# BrakePlaus2019.net
KiCad netlist of a schematic drawn in Altium Designer
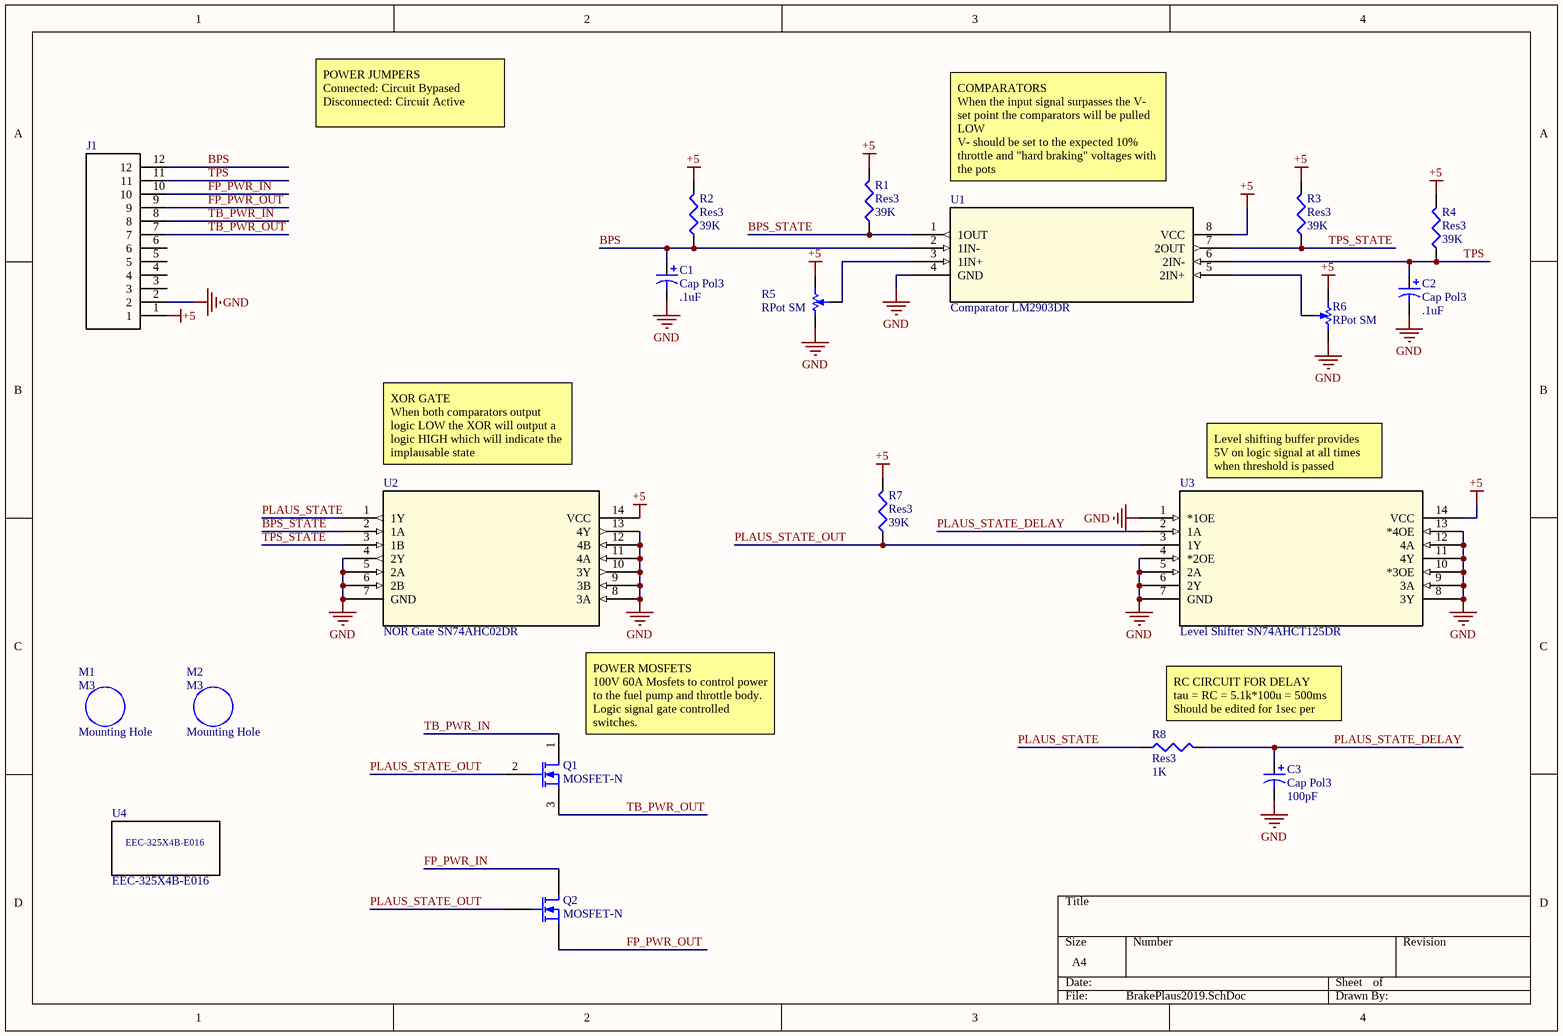
[diagram p0: BrakePlaus2019.SchDoc]

(export (version "E")
  (design (tool "Eeschema 10.0.6"))
  (components
    (comp (ref "C1")
      (value "Cap Pol3")
      (footprint "C0805")
      (description "Polarized Capacitor (Surface Mount)")
      (fields (field (name "ALTIUM_VALUE") ".1uF") (field (name "PUBLISHER") "Altium Limited"))
      (libsource (lib "Miscellaneous Devices") (part "Cap Pol3"))
    )
    (comp (ref "C2")
      (value "Cap Pol3")
      (footprint "C0805")
      (description "Polarized Capacitor (Surface Mount)")
      (fields (field (name "ALTIUM_VALUE") ".1uF") (field (name "PUBLISHER") "Altium Limited"))
      (libsource (lib "Miscellaneous Devices") (part "Cap Pol3"))
    )
    (comp (ref "C3")
      (value "Cap Pol3")
      (footprint "C0805")
      (description "Polarized Capacitor (Surface Mount)")
      (fields (field (name "ALTIUM_VALUE") "100pF") (field (name "PUBLISHER") "Altium Limited"))
      (libsource (lib "Miscellaneous Devices") (part "Cap Pol3"))
    )
    (comp (ref "J1")
      (value "DTM13-12PA-R008")
      (footprint "*TE_DTM13-12PA-R008")
      (description "DTM Series, 4.19mm Pitch 12 Way 2 Row Right Angle PCB Header, Solder Termination")
      (fields (field (name "MF") "TE Connectivity") (field (name "DIGI-KEY_PART_NUMBER") "1734-1130-ND"))
      (libsource (lib "DTM13-12PA-R008") (part "DTM13-12PA-R008"))
    )
    (comp (ref "M1")
      (value "Mounting Hole")
      (footprint "M3 Mounting Hole")
      (libsource (lib "BrakePlaus2019") (part "M3 Mounting Hole"))
    )
    (comp (ref "M2")
      (value "Mounting Hole")
      (footprint "M3 Mounting Hole")
      (libsource (lib "BrakePlaus2019") (part "M3 Mounting Hole"))
    )
    (comp (ref "Q1")
      (value "MOSFET-N")
      (footprint "DPAK")
      (description "N-Channel MOSFET")
      (fields (field (name "PUBLISHER") "Altium Limited"))
      (libsource (lib "Miscellaneous Devices") (part "MOSFET-N"))
    )
    (comp (ref "Q2")
      (value "MOSFET-N")
      (footprint "DPAK")
      (description "N-Channel MOSFET")
      (fields (field (name "PUBLISHER") "Altium Limited"))
      (libsource (lib "") (part "MOSFET-N_1"))
    )
    (comp (ref "R1")
      (value "Res3")
      (footprint "J1-0603")
      (description "Resistor")
      (fields (field (name "ALTIUM_VALUE") "39K") (field (name "PUBLISHER") "Altium Limited"))
      (libsource (lib "Miscellaneous Devices") (part "Res3"))
    )
    (comp (ref "R2")
      (value "Res3")
      (footprint "J1-0603")
      (description "Resistor")
      (fields (field (name "ALTIUM_VALUE") "39K") (field (name "PUBLISHER") "Altium Limited"))
      (libsource (lib "Miscellaneous Devices") (part "Res3"))
    )
    (comp (ref "R3")
      (value "Res3")
      (footprint "J1-0603")
      (description "Resistor")
      (fields (field (name "ALTIUM_VALUE") "39K") (field (name "PUBLISHER") "Altium Limited"))
      (libsource (lib "Miscellaneous Devices") (part "Res3"))
    )
    (comp (ref "R4")
      (value "Res3")
      (footprint "J1-0603")
      (description "Resistor")
      (fields (field (name "ALTIUM_VALUE") "39K") (field (name "PUBLISHER") "Altium Limited"))
      (libsource (lib "Miscellaneous Devices") (part "Res3"))
    )
    (comp (ref "R5")
      (value "RPot SM")
      (footprint "POT4MM-2")
      (description "Square Trimming Potentiometer")
      (fields (field (name "PUBLISHER") "Altium Limited"))
      (libsource (lib "Miscellaneous Devices") (part "RPot SM"))
    )
    (comp (ref "R6")
      (value "RPot SM")
      (footprint "POT4MM-2")
      (description "Square Trimming Potentiometer")
      (fields (field (name "PUBLISHER") "Altium Limited"))
      (libsource (lib "Miscellaneous Devices") (part "RPot SM"))
    )
    (comp (ref "R7")
      (value "Res3")
      (footprint "J1-0603")
      (description "Resistor")
      (fields (field (name "ALTIUM_VALUE") "39K") (field (name "PUBLISHER") "Altium Limited"))
      (libsource (lib "Miscellaneous Devices") (part "Res3"))
    )
    (comp (ref "R8")
      (value "Res3")
      (footprint "J1-0603")
      (description "Resistor")
      (fields (field (name "ALTIUM_VALUE") "1K") (field (name "PUBLISHER") "Altium Limited"))
      (libsource (lib "Miscellaneous Devices") (part "Res3"))
    )
    (comp (ref "U1")
      (value "Comparator LM2903DR")
      (footprint "D8")
      (description "Comparator")
      (fields
        (field (name "MANUFACTURER") "Texas Instruments")
        (field (name "MANUFACTURER_PART_NUMBER") "LM2903DR")
        (field (name "COPYRIGHT") "Copyright (C) 2018 Accelerated Designs. All rights reserved")
      )
      (libsource (lib "2019-02-10_01-57-59") (part "LM2903DR"))
    )
    (comp (ref "U2")
      (value "NOR Gate SN74AHC02DR")
      (footprint "D14")
      (description "Quad 2 Input NOR Gate")
      (fields
        (field (name "MANUFACTURER") "Texas Instruments")
        (field (name "MANUFACTURER_PART_NUMBER") "SN74AHC02DR")
        (field (name "COPYRIGHT") "Copyright (C) 2018 Accelerated Designs. All rights reserved")
      )
      (libsource (lib "2019-02-10_02-17-19") (part "NOR Gate"))
    )
    (comp (ref "U3")
      (value "Level Shifter SN74AHCT125DR")
      (footprint "D14")
      (description "Buffer (Level Shifter)")
      (fields
        (field (name "MANUFACTURER") "Texas Instruments")
        (field (name "MANUFACTURER_PART_NUMBER") "SN74AHCT125DR")
        (field (name "COPYRIGHT") "Copyright (C) 2018 Accelerated Designs. All rights reserved")
      )
      (libsource (lib "2019-02-10_02-08-30") (part "SN74AHCT125DR"))
    )
    (comp (ref "U4")
      (value "EEC-325X4B-E016")
      (footprint "*TE_EEC-325X4B-E016")
      (libsource (lib "EEC-325X4B-E016") (part "EEC-325X4B-E016"))
    )
  )
  (nets
    (net (code "1") (name "+5") (class "Default")
      (node (ref "J1") (pin "1") (pinfunction "1_1") (pintype "passive"))
      (node (ref "R1") (pin "2") (pinfunction "2_2") (pintype "passive"))
      (node (ref "R2") (pin "2") (pinfunction "2_2") (pintype "passive"))
      (node (ref "R3") (pin "2") (pinfunction "2_2") (pintype "passive"))
      (node (ref "R4") (pin "2") (pinfunction "2_2") (pintype "passive"))
      (node (ref "R5") (pin "CW") (pinfunction "+_CW") (pintype "passive"))
      (node (ref "R6") (pin "CCW") (pinfunction "-_CCW") (pintype "passive"))
      (node (ref "R7") (pin "2") (pinfunction "2_2") (pintype "passive"))
      (node (ref "U1") (pin "8") (pinfunction "VCC_8") (pintype "power_in"))
      (node (ref "U2") (pin "14") (pinfunction "VCC_14") (pintype "power_in"))
      (node (ref "U3") (pin "14") (pinfunction "VCC_14") (pintype "power_in"))
    )
    (net (code "2") (name "/BPS") (class "Default")
      (node (ref "C1") (pin "1") (pinfunction "1_1") (pintype "passive"))
      (node (ref "J1") (pin "12") (pinfunction "12_12") (pintype "passive"))
      (node (ref "R2") (pin "1") (pinfunction "1_1") (pintype "passive"))
      (node (ref "U1") (pin "2") (pinfunction "1IN-_2") (pintype "input"))
    )
    (net (code "3") (name "/BPS_STATE") (class "Default")
      (node (ref "R1") (pin "1") (pinfunction "1_1") (pintype "passive"))
      (node (ref "U1") (pin "1") (pinfunction "1OUT_1") (pintype "output"))
      (node (ref "U2") (pin "2") (pinfunction "1A_2") (pintype "input"))
    )
    (net (code "4") (name "/FP_PWR_IN") (class "Default")
      (node (ref "J1") (pin "10") (pinfunction "10_10") (pintype "passive"))
      (node (ref "Q2") (pin "1") (pinfunction "D_1") (pintype "passive"))
    )
    (net (code "5") (name "/FP_PWR_OUT") (class "Default")
      (node (ref "J1") (pin "9") (pinfunction "9_9") (pintype "passive"))
      (node (ref "Q2") (pin "3") (pinfunction "S_3") (pintype "passive"))
    )
    (net (code "6") (name "/PLAUS_STATE") (class "Default")
      (node (ref "R8") (pin "1") (pinfunction "1_1") (pintype "passive"))
      (node (ref "U2") (pin "1") (pinfunction "1Y_1") (pintype "output"))
    )
    (net (code "7") (name "/PLAUS_STATE_DELAY") (class "Default")
      (node (ref "C3") (pin "1") (pinfunction "1_1") (pintype "passive"))
      (node (ref "R8") (pin "2") (pinfunction "2_2") (pintype "passive"))
      (node (ref "U3") (pin "2") (pinfunction "1A_2") (pintype "input"))
    )
    (net (code "8") (name "/PLAUS_STATE_OUT") (class "Default")
      (node (ref "Q1") (pin "2") (pinfunction "G_2") (pintype "passive"))
      (node (ref "Q2") (pin "2") (pinfunction "G_2") (pintype "passive"))
      (node (ref "R7") (pin "1") (pinfunction "1_1") (pintype "passive"))
      (node (ref "U3") (pin "3") (pinfunction "1Y_3") (pintype "passive"))
    )
    (net (code "9") (name "/TB_PWR_IN") (class "Default")
      (node (ref "J1") (pin "8") (pinfunction "8_8") (pintype "passive"))
      (node (ref "Q1") (pin "1") (pinfunction "D_1") (pintype "passive"))
    )
    (net (code "10") (name "/TB_PWR_OUT") (class "Default")
      (node (ref "J1") (pin "7") (pinfunction "7_7") (pintype "passive"))
      (node (ref "Q1") (pin "3") (pinfunction "S_3") (pintype "passive"))
    )
    (net (code "11") (name "/TPS") (class "Default")
      (node (ref "C2") (pin "1") (pinfunction "1_1") (pintype "passive"))
      (node (ref "J1") (pin "11") (pinfunction "11_11") (pintype "passive"))
      (node (ref "R4") (pin "1") (pinfunction "1_1") (pintype "passive"))
      (node (ref "U1") (pin "6") (pinfunction "2IN-_6") (pintype "input"))
    )
    (net (code "12") (name "/TPS_STATE") (class "Default")
      (node (ref "R3") (pin "1") (pinfunction "1_1") (pintype "passive"))
      (node (ref "U1") (pin "7") (pinfunction "2OUT_7") (pintype "output"))
      (node (ref "U2") (pin "3") (pinfunction "1B_3") (pintype "input"))
    )
    (net (code "13") (name "GND") (class "Default")
      (node (ref "C1") (pin "2") (pinfunction "2_2") (pintype "passive"))
      (node (ref "C2") (pin "2") (pinfunction "2_2") (pintype "passive"))
      (node (ref "C3") (pin "2") (pinfunction "2_2") (pintype "passive"))
      (node (ref "J1") (pin "2") (pinfunction "2_2") (pintype "passive"))
      (node (ref "R5") (pin "CCW") (pinfunction "-_CCW") (pintype "passive"))
      (node (ref "R6") (pin "CW") (pinfunction "+_CW") (pintype "passive"))
      (node (ref "U1") (pin "4") (pinfunction "GND_4") (pintype "power_in"))
      (node (ref "U2") (pin "10") (pinfunction "3Y_10") (pintype "output"))
      (node (ref "U2") (pin "11") (pinfunction "4A_11") (pintype "input"))
      (node (ref "U2") (pin "12") (pinfunction "4B_12") (pintype "input"))
      (node (ref "U2") (pin "13") (pinfunction "4Y_13") (pintype "output"))
      (node (ref "U2") (pin "4") (pinfunction "2Y_4") (pintype "output"))
      (node (ref "U2") (pin "5") (pinfunction "2A_5") (pintype "input"))
      (node (ref "U2") (pin "6") (pinfunction "2B_6") (pintype "input"))
      (node (ref "U2") (pin "7") (pinfunction "GND_7") (pintype "power_in"))
      (node (ref "U2") (pin "8") (pinfunction "3A_8") (pintype "input"))
      (node (ref "U2") (pin "9") (pinfunction "3B_9") (pintype "input"))
      (node (ref "U3") (pin "1") (pinfunction "*1OE_1") (pintype "input"))
      (node (ref "U3") (pin "10") (pinfunction "*3OE_10") (pintype "input"))
      (node (ref "U3") (pin "11") (pinfunction "4Y_11") (pintype "passive"))
      (node (ref "U3") (pin "12") (pinfunction "4A_12") (pintype "input"))
      (node (ref "U3") (pin "13") (pinfunction "*4OE_13") (pintype "input"))
      (node (ref "U3") (pin "4") (pinfunction "*2OE_4") (pintype "input"))
      (node (ref "U3") (pin "5") (pinfunction "2A_5") (pintype "input"))
      (node (ref "U3") (pin "6") (pinfunction "2Y_6") (pintype "passive"))
      (node (ref "U3") (pin "7") (pinfunction "GND_7") (pintype "power_in"))
      (node (ref "U3") (pin "8") (pinfunction "3Y_8") (pintype "passive"))
      (node (ref "U3") (pin "9") (pinfunction "3A_9") (pintype "input"))
    )
    (net (code "14") (name "Net-(U1-1IN+)") (class "Default")
      (node (ref "R5") (pin "W") (pinfunction "W_W") (pintype "passive"))
      (node (ref "U1") (pin "3") (pinfunction "1IN+_3") (pintype "input"))
    )
    (net (code "15") (name "Net-(U1-2IN+)") (class "Default")
      (node (ref "R6") (pin "W") (pinfunction "W_W") (pintype "passive"))
      (node (ref "U1") (pin "5") (pinfunction "2IN+_5") (pintype "input"))
    )
    (net (code "16") (name "unconnected-(J1-Pad3)") (class "Default")
      (node (ref "J1") (pin "3") (pinfunction "3_3") (pintype "passive"))
    )
    (net (code "17") (name "unconnected-(J1-Pad4)") (class "Default")
      (node (ref "J1") (pin "4") (pinfunction "4_4") (pintype "passive"))
    )
    (net (code "18") (name "unconnected-(J1-Pad5)") (class "Default")
      (node (ref "J1") (pin "5") (pinfunction "5_5") (pintype "passive"))
    )
    (net (code "19") (name "unconnected-(J1-Pad6)") (class "Default")
      (node (ref "J1") (pin "6") (pinfunction "6_6") (pintype "passive"))
    )
  )
)
